# hw2.net
KiCad netlist of a schematic drawn in EAGLE
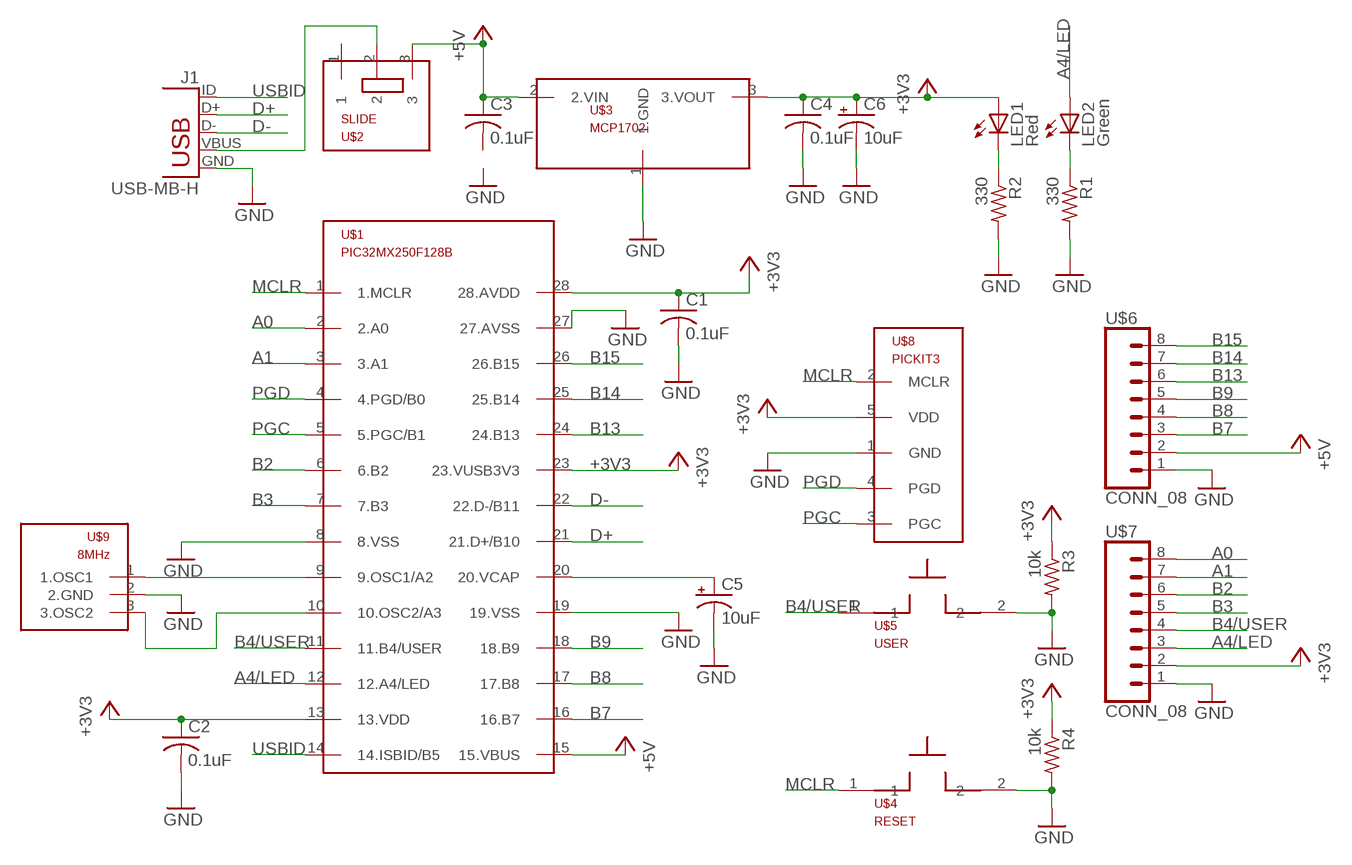
[diagram p0: schematic, sheet 1]

(export (version "E")
  (design (tool "Eeschema 10.0.6"))
  (components
    (comp (ref "C1")
      (value "0.1uF")
      (footprint "eagle-import:C025-025X050")
      (libsource (lib "eagle-import") (part "C-US025-025X050"))
    )
    (comp (ref "C2")
      (value "0.1uF")
      (footprint "eagle-import:C025-025X050")
      (libsource (lib "eagle-import") (part "C-US025-025X050"))
    )
    (comp (ref "C3")
      (value "0.1uF")
      (footprint "eagle-import:C025-025X050")
      (libsource (lib "eagle-import") (part "C-US025-025X050"))
    )
    (comp (ref "C4")
      (value "0.1uF")
      (footprint "eagle-import:C025-025X050")
      (libsource (lib "eagle-import") (part "C-US025-025X050"))
    )
    (comp (ref "C5")
      (value "10uF")
      (footprint "eagle-import:B45181B")
      (libsource (lib "eagle-import") (part "CPOL-USB45181B"))
    )
    (comp (ref "C6")
      (value "10uF")
      (footprint "eagle-import:B45181B")
      (libsource (lib "eagle-import") (part "CPOL-USB45181B"))
    )
    (comp (ref "J1")
      (value "USB-MB-H")
      (footprint "eagle-import:USB-MB-H")
      (libsource (lib "eagle-import") (part "USB-MB-H"))
    )
    (comp (ref "LED1")
      (value "Red")
      (footprint "eagle-import:LED3MM")
      (libsource (lib "eagle-import") (part "LED3MM"))
    )
    (comp (ref "LED2")
      (value "Green")
      (footprint "eagle-import:LED3MM")
      (libsource (lib "eagle-import") (part "LED3MM"))
    )
    (comp (ref "R1")
      (value "330")
      (footprint "eagle-import:0207_10")
      (libsource (lib "eagle-import") (part "R-US_0207/10"))
    )
    (comp (ref "R2")
      (value "330")
      (footprint "eagle-import:0207_10")
      (libsource (lib "eagle-import") (part "R-US_0207/10"))
    )
    (comp (ref "R3")
      (value "10k")
      (footprint "eagle-import:0207_10")
      (libsource (lib "eagle-import") (part "R-US_0207/10"))
    )
    (comp (ref "R4")
      (value "10k")
      (footprint "eagle-import:0207_10")
      (libsource (lib "eagle-import") (part "R-US_0207/10"))
    )
    (comp (ref "U$1")
      (value "PIC32MX250F128B")
      (footprint "eagle-import:DIL28-3")
      (libsource (lib "eagle-import") (part "PIC32MX250F128B"))
    )
    (comp (ref "U$2")
      (value "SLIDE")
      (footprint "eagle-import:SLIDE")
      (libsource (lib "eagle-import") (part "SLIDE"))
    )
    (comp (ref "U$3")
      (value "MCP1702")
      (footprint "eagle-import:TO92")
      (libsource (lib "eagle-import") (part "MCP1702"))
    )
    (comp (ref "U$4")
      (value "RESET")
      (footprint "eagle-import:PB")
      (libsource (lib "eagle-import") (part "PB"))
    )
    (comp (ref "U$5")
      (value "USER")
      (footprint "eagle-import:PB")
      (libsource (lib "eagle-import") (part "PB"))
    )
    (comp (ref "U$6")
      (value "CONN_08")
      (footprint "eagle-import:1X08")
      (libsource (lib "eagle-import") (part "CONN_08"))
    )
    (comp (ref "U$7")
      (value "CONN_08")
      (footprint "eagle-import:1X08")
      (libsource (lib "eagle-import") (part "CONN_08"))
    )
    (comp (ref "U$8")
      (value "PICKIT3")
      (footprint "eagle-import:1X05")
      (libsource (lib "eagle-import") (part "PICKIT3"))
    )
    (comp (ref "U$9")
      (value "8MHz")
      (footprint "eagle-import:OSC")
      (libsource (lib "eagle-import") (part "OSCOSC"))
    )
  )
  (nets
    (net (code "1") (name "+3V3") (class "Default")
      (node (ref "C1") (pin "1") (pinfunction "1_1") (pintype "passive"))
      (node (ref "C2") (pin "1") (pinfunction "1_1") (pintype "passive"))
      (node (ref "C4") (pin "1") (pinfunction "1_1") (pintype "passive"))
      (node (ref "C6") (pin "+") (pinfunction "+_+") (pintype "passive"))
      (node (ref "LED1") (pin "A") (pinfunction "A_A") (pintype "passive"))
      (node (ref "R3") (pin "1") (pinfunction "1_1") (pintype "passive"))
      (node (ref "R4") (pin "1") (pinfunction "1_1") (pintype "passive"))
      (node (ref "U$1") (pin "13") (pinfunction "13.VDD_13") (pintype "bidirectional"))
      (node (ref "U$1") (pin "23") (pinfunction "23.VUSB3V3_23") (pintype "bidirectional"))
      (node (ref "U$1") (pin "28") (pinfunction "28.AVDD_28") (pintype "bidirectional"))
      (node (ref "U$3") (pin "3") (pinfunction "3.VOUT_3") (pintype "bidirectional"))
      (node (ref "U$7") (pin "2") (pinfunction "2_2") (pintype "passive"))
      (node (ref "U$8") (pin "5") (pinfunction "VDD_5") (pintype "bidirectional"))
    )
    (net (code "2") (name "+5V") (class "Default")
      (node (ref "C3") (pin "1") (pinfunction "1_1") (pintype "passive"))
      (node (ref "U$1") (pin "15") (pinfunction "15.VBUS_15") (pintype "bidirectional"))
      (node (ref "U$2") (pin "3") (pinfunction "3_3") (pintype "bidirectional"))
      (node (ref "U$3") (pin "2") (pinfunction "2.VIN_2") (pintype "bidirectional"))
      (node (ref "U$6") (pin "2") (pinfunction "2_2") (pintype "passive"))
    )
    (net (code "3") (name "/A0") (class "Default")
      (node (ref "U$1") (pin "2") (pinfunction "2.A0_2") (pintype "bidirectional"))
      (node (ref "U$7") (pin "8") (pinfunction "8_8") (pintype "passive"))
    )
    (net (code "4") (name "/A1") (class "Default")
      (node (ref "U$1") (pin "3") (pinfunction "3.A1_3") (pintype "bidirectional"))
      (node (ref "U$7") (pin "7") (pinfunction "7_7") (pintype "passive"))
    )
    (net (code "5") (name "/A4{slash}LED") (class "Default")
      (node (ref "LED2") (pin "A") (pinfunction "A_A") (pintype "passive"))
      (node (ref "U$1") (pin "12") (pinfunction "12.A4/LED_12") (pintype "bidirectional"))
      (node (ref "U$7") (pin "3") (pinfunction "3_3") (pintype "passive"))
    )
    (net (code "6") (name "/B2") (class "Default")
      (node (ref "U$1") (pin "6") (pinfunction "6.B2_6") (pintype "bidirectional"))
      (node (ref "U$7") (pin "6") (pinfunction "6_6") (pintype "passive"))
    )
    (net (code "7") (name "/B3") (class "Default")
      (node (ref "U$1") (pin "7") (pinfunction "7.B3_7") (pintype "bidirectional"))
      (node (ref "U$7") (pin "5") (pinfunction "5_5") (pintype "passive"))
    )
    (net (code "8") (name "/B4{slash}USER") (class "Default")
      (node (ref "U$1") (pin "11") (pinfunction "11.B4/USER_11") (pintype "bidirectional"))
      (node (ref "U$5") (pin "1") (pinfunction "1_1") (pintype "bidirectional"))
      (node (ref "U$7") (pin "4") (pinfunction "4_4") (pintype "passive"))
    )
    (net (code "9") (name "/B7") (class "Default")
      (node (ref "U$1") (pin "16") (pinfunction "16.B7_16") (pintype "bidirectional"))
      (node (ref "U$6") (pin "3") (pinfunction "3_3") (pintype "passive"))
    )
    (net (code "10") (name "/B8") (class "Default")
      (node (ref "U$1") (pin "17") (pinfunction "17.B8_17") (pintype "bidirectional"))
      (node (ref "U$6") (pin "4") (pinfunction "4_4") (pintype "passive"))
    )
    (net (code "11") (name "/B9") (class "Default")
      (node (ref "U$1") (pin "18") (pinfunction "18.B9_18") (pintype "bidirectional"))
      (node (ref "U$6") (pin "5") (pinfunction "5_5") (pintype "passive"))
    )
    (net (code "12") (name "/B13") (class "Default")
      (node (ref "U$1") (pin "24") (pinfunction "24.B13_24") (pintype "bidirectional"))
      (node (ref "U$6") (pin "6") (pinfunction "6_6") (pintype "passive"))
    )
    (net (code "13") (name "/B14") (class "Default")
      (node (ref "U$1") (pin "25") (pinfunction "25.B14_25") (pintype "bidirectional"))
      (node (ref "U$6") (pin "7") (pinfunction "7_7") (pintype "passive"))
    )
    (net (code "14") (name "/B15") (class "Default")
      (node (ref "U$1") (pin "26") (pinfunction "26.B15_26") (pintype "bidirectional"))
      (node (ref "U$6") (pin "8") (pinfunction "8_8") (pintype "passive"))
    )
    (net (code "15") (name "/D+") (class "Default")
      (node (ref "J1") (pin "D+") (pinfunction "D+_D+") (pintype "bidirectional"))
      (node (ref "U$1") (pin "21") (pinfunction "21.D+/B10_21") (pintype "bidirectional"))
    )
    (net (code "16") (name "/D-") (class "Default")
      (node (ref "J1") (pin "D-") (pinfunction "D-_D-") (pintype "bidirectional"))
      (node (ref "U$1") (pin "22") (pinfunction "22.D-/B11_22") (pintype "bidirectional"))
    )
    (net (code "17") (name "/MCLR") (class "Default")
      (node (ref "U$1") (pin "1") (pinfunction "1.MCLR_1") (pintype "bidirectional"))
      (node (ref "U$4") (pin "1") (pinfunction "1_1") (pintype "bidirectional"))
      (node (ref "U$8") (pin "2") (pinfunction "MCLR_2") (pintype "bidirectional"))
    )
    (net (code "18") (name "/PGC") (class "Default")
      (node (ref "U$1") (pin "5") (pinfunction "5.PGC/B1_5") (pintype "bidirectional"))
      (node (ref "U$8") (pin "3") (pinfunction "PGC_3") (pintype "bidirectional"))
    )
    (net (code "19") (name "/PGD") (class "Default")
      (node (ref "U$1") (pin "4") (pinfunction "4.PGD/B0_4") (pintype "bidirectional"))
      (node (ref "U$8") (pin "4") (pinfunction "PGD_4") (pintype "bidirectional"))
    )
    (net (code "20") (name "/USBID") (class "Default")
      (node (ref "J1") (pin "ID") (pinfunction "ID_ID") (pintype "bidirectional"))
      (node (ref "U$1") (pin "14") (pinfunction "14.ISBID/B5_14") (pintype "bidirectional"))
    )
    (net (code "21") (name "GND") (class "Default")
      (node (ref "C1") (pin "2") (pinfunction "2_2") (pintype "passive"))
      (node (ref "C2") (pin "2") (pinfunction "2_2") (pintype "passive"))
      (node (ref "C4") (pin "2") (pinfunction "2_2") (pintype "passive"))
      (node (ref "C5") (pin "-") (pinfunction "-_-") (pintype "passive"))
      (node (ref "C6") (pin "-") (pinfunction "-_-") (pintype "passive"))
      (node (ref "J1") (pin "GND") (pinfunction "GND_GND") (pintype "bidirectional"))
      (node (ref "R1") (pin "2") (pinfunction "2_2") (pintype "passive"))
      (node (ref "R2") (pin "2") (pinfunction "2_2") (pintype "passive"))
      (node (ref "R3") (pin "2") (pinfunction "2_2") (pintype "passive"))
      (node (ref "R4") (pin "2") (pinfunction "2_2") (pintype "passive"))
      (node (ref "U$1") (pin "19") (pinfunction "19.VSS_19") (pintype "bidirectional"))
      (node (ref "U$1") (pin "27") (pinfunction "27.AVSS_27") (pintype "bidirectional"))
      (node (ref "U$1") (pin "8") (pinfunction "8.VSS_8") (pintype "bidirectional"))
      (node (ref "U$3") (pin "1") (pinfunction "1.GND_1") (pintype "bidirectional"))
      (node (ref "U$4") (pin "2") (pinfunction "2_2") (pintype "bidirectional"))
      (node (ref "U$5") (pin "2") (pinfunction "2_2") (pintype "bidirectional"))
      (node (ref "U$6") (pin "1") (pinfunction "1_1") (pintype "passive"))
      (node (ref "U$7") (pin "1") (pinfunction "1_1") (pintype "passive"))
      (node (ref "U$8") (pin "1") (pinfunction "GND_1") (pintype "bidirectional"))
      (node (ref "U$9") (pin "2") (pinfunction "2.GND_2") (pintype "bidirectional"))
    )
    (net (code "22") (name "Net-(J1-PadVBUS)") (class "Default")
      (node (ref "J1") (pin "VBUS") (pinfunction "VBUS_VBUS") (pintype "bidirectional"))
      (node (ref "U$2") (pin "2") (pinfunction "2_2") (pintype "bidirectional"))
    )
    (net (code "23") (name "Net-(LED1-C)") (class "Default")
      (node (ref "LED1") (pin "K") (pinfunction "C_K") (pintype "passive"))
      (node (ref "R2") (pin "1") (pinfunction "1_1") (pintype "passive"))
    )
    (net (code "24") (name "Net-(LED2-C)") (class "Default")
      (node (ref "LED2") (pin "K") (pinfunction "C_K") (pintype "passive"))
      (node (ref "R1") (pin "1") (pinfunction "1_1") (pintype "passive"))
    )
    (net (code "25") (name "Net-(U$1-9.OSC1{slash}A2)") (class "Default")
      (node (ref "U$1") (pin "9") (pinfunction "9.OSC1/A2_9") (pintype "bidirectional"))
      (node (ref "U$9") (pin "1") (pinfunction "1.OSC1_1") (pintype "bidirectional"))
    )
    (net (code "26") (name "Net-(U$1-10.OSC2{slash}A3)") (class "Default")
      (node (ref "U$1") (pin "10") (pinfunction "10.OSC2/A3_10") (pintype "bidirectional"))
      (node (ref "U$9") (pin "3") (pinfunction "3.OSC2_3") (pintype "bidirectional"))
    )
    (net (code "27") (name "Net-(U$1-20.VCAP)") (class "Default")
      (node (ref "C5") (pin "+") (pinfunction "+_+") (pintype "passive"))
      (node (ref "U$1") (pin "20") (pinfunction "20.VCAP_20") (pintype "bidirectional"))
    )
    (net (code "28") (name "unconnected-(C3-Pad2)") (class "Default")
      (node (ref "C3") (pin "2") (pinfunction "2_2") (pintype "passive"))
    )
    (net (code "29") (name "unconnected-(U$2-Pad1)") (class "Default")
      (node (ref "U$2") (pin "1") (pinfunction "1_1") (pintype "bidirectional"))
    )
  )
)
